# Arduino-Pro-Mini.net
KiCad netlist of a schematic drawn in EAGLE
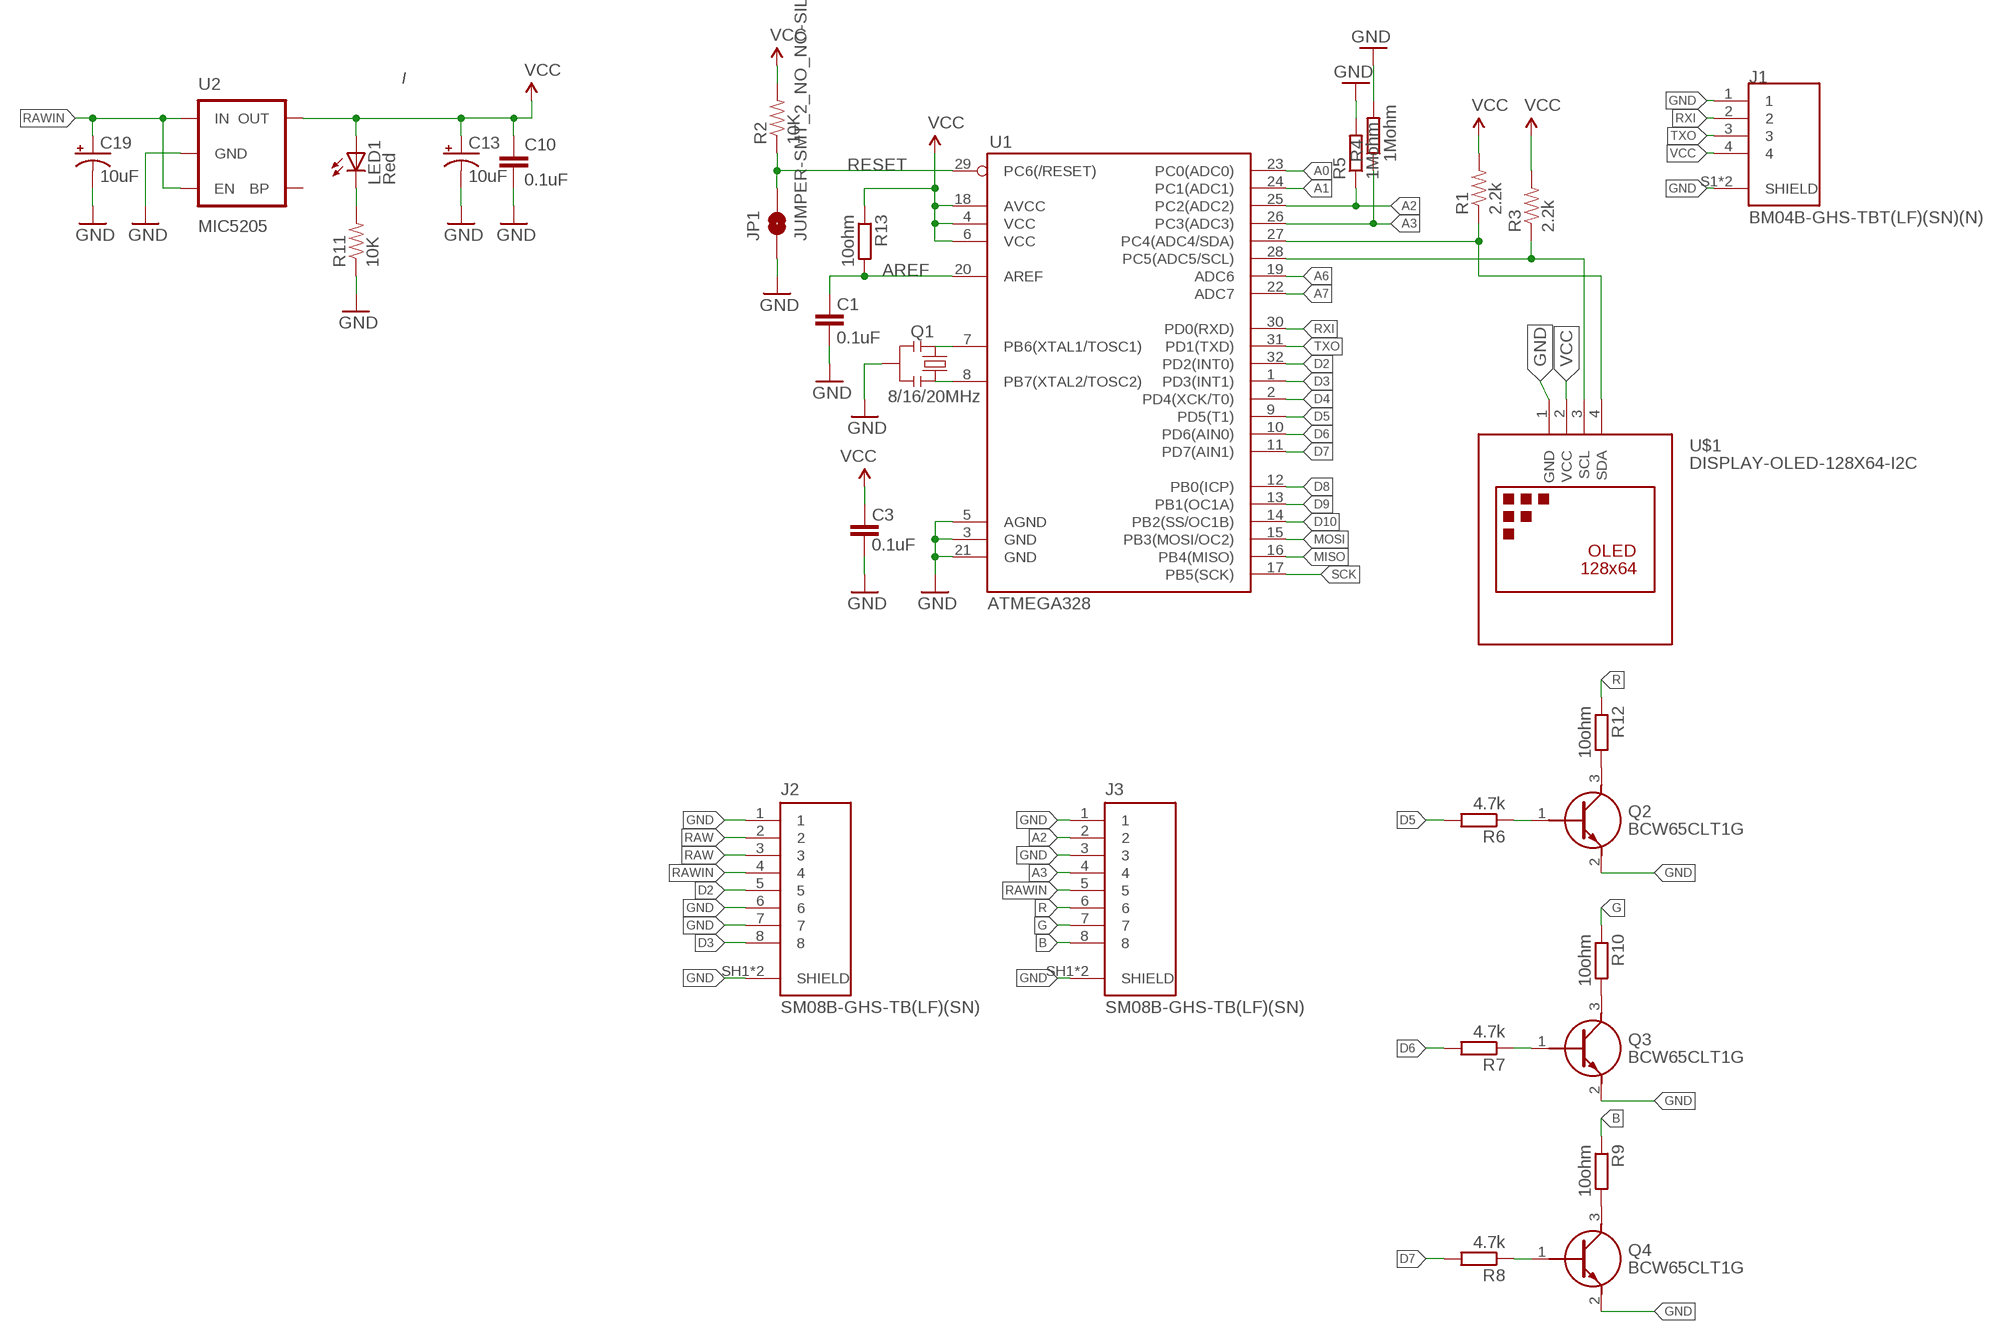
[diagram p0: schematic, sheet 1]

(export (version "E")
  (design (tool "Eeschema 10.0.6"))
  (components
    (comp (ref "C1")
      (value "0.1uF")
      (footprint "eagle-import:0603-CAP")
      (libsource (lib "eagle-import") (part "CAP0603-CAP"))
    )
    (comp (ref "C3")
      (value "0.1uF")
      (footprint "eagle-import:0603-CAP")
      (libsource (lib "eagle-import") (part "CAP0603-CAP"))
    )
    (comp (ref "C10")
      (value "0.1uF")
      (footprint "eagle-import:0603-CAP")
      (libsource (lib "eagle-import") (part "CAP0603-CAP"))
    )
    (comp (ref "C13")
      (value "10uF")
      (footprint "eagle-import:EIA3216")
      (libsource (lib "eagle-import") (part "CAP_POL1206"))
    )
    (comp (ref "C19")
      (value "10uF")
      (footprint "eagle-import:EIA3216")
      (libsource (lib "eagle-import") (part "CAP_POL1206"))
    )
    (comp (ref "J1")
      (value "BM04B-GHS-TBT(LF)(SN)(N)")
      (footprint "eagle-import:JST_BM04B-GHS-TBT(LF)(SN)(N)")
      (fields (field (name "MF") "JST Sales") (field (name "MP") "BM04B-GHS-TBT_LF__SN__N_"))
      (libsource (lib "eagle-import") (part "BM04B-GHS-TBT(LF)(SN)(N)"))
    )
    (comp (ref "J2")
      (value "SM08B-GHS-TB(LF)(SN)")
      (footprint "eagle-import:JST_SM08B-GHS-TB(LF)(SN)")
      (fields (field (name "MF") "JST Sales") (field (name "MP") "SM08B-GHS-TB_LF__SN_"))
      (libsource (lib "eagle-import") (part "SM08B-GHS-TB(LF)(SN)"))
    )
    (comp (ref "J3")
      (value "SM08B-GHS-TB(LF)(SN)")
      (footprint "eagle-import:JST_SM08B-GHS-TB(LF)(SN)")
      (fields (field (name "MF") "JST Sales") (field (name "MP") "SM08B-GHS-TB_LF__SN_"))
      (libsource (lib "eagle-import") (part "SM08B-GHS-TB(LF)(SN)"))
    )
    (comp (ref "JP1")
      (value "JUMPER-SMT_2_NO_NO-SILK")
      (footprint "eagle-import:SMT-JUMPER_2_NO_NO-SILK")
      (libsource (lib "eagle-import") (part "JUMPER-SMT_2_NO_NO-SILK"))
    )
    (comp (ref "LED1")
      (value "Red")
      (footprint "eagle-import:0603-LED-ALT1")
      (libsource (lib "eagle-import") (part "LED"))
    )
    (comp (ref "Q1")
      (value "8/16/20MHz")
      (footprint "eagle-import:RESONATOR-SMD-1_1")
      (libsource (lib "eagle-import") (part "RESONATOR1{colon}1"))
    )
    (comp (ref "Q2")
      (value "BCW65CLT1G")
      (footprint "eagle-import:SOT96P237X111-3N")
      (fields (field (name "MOUSER_PART_NUMBER") "863-BCW65CLT1G") (field (name "RS_PART_NUMBER") "8009686P"))
      (libsource (lib "eagle-import") (part "BCW65CLT1G"))
    )
    (comp (ref "Q3")
      (value "BCW65CLT1G")
      (footprint "eagle-import:SOT96P237X111-3N")
      (fields (field (name "MOUSER_PART_NUMBER") "863-BCW65CLT1G") (field (name "RS_PART_NUMBER") "8009686P"))
      (libsource (lib "eagle-import") (part "BCW65CLT1G"))
    )
    (comp (ref "Q4")
      (value "BCW65CLT1G")
      (footprint "eagle-import:SOT96P237X111-3N")
      (fields (field (name "MOUSER_PART_NUMBER") "863-BCW65CLT1G") (field (name "RS_PART_NUMBER") "8009686P"))
      (libsource (lib "eagle-import") (part "BCW65CLT1G"))
    )
    (comp (ref "R1")
      (value "2.2k")
      (footprint "eagle-import:0603-RES")
      (libsource (lib "eagle-import") (part "RESISTOR0603-RES"))
    )
    (comp (ref "R2")
      (value "10K")
      (footprint "eagle-import:0603-RES")
      (libsource (lib "eagle-import") (part "RESISTOR0603-RES"))
    )
    (comp (ref "R3")
      (value "2.2k")
      (footprint "eagle-import:0603-RES")
      (libsource (lib "eagle-import") (part "RESISTOR0603-RES"))
    )
    (comp (ref "R4")
      (value "1Mohm")
      (footprint "eagle-import:R0402")
      (libsource (lib "eagle-import") (part "RR0402"))
    )
    (comp (ref "R5")
      (value "1Mohm")
      (footprint "eagle-import:R0402")
      (libsource (lib "eagle-import") (part "RR0402"))
    )
    (comp (ref "R6")
      (value "4.7k")
      (footprint "eagle-import:R0402")
      (libsource (lib "eagle-import") (part "RR0402"))
    )
    (comp (ref "R7")
      (value "4.7k")
      (footprint "eagle-import:R0402")
      (libsource (lib "eagle-import") (part "RR0402"))
    )
    (comp (ref "R8")
      (value "4.7k")
      (footprint "eagle-import:R0402")
      (libsource (lib "eagle-import") (part "RR0402"))
    )
    (comp (ref "R9")
      (value "10ohm")
      (footprint "eagle-import:R0402")
      (libsource (lib "eagle-import") (part "RR0402"))
    )
    (comp (ref "R10")
      (value "10ohm")
      (footprint "eagle-import:R0402")
      (libsource (lib "eagle-import") (part "RR0402"))
    )
    (comp (ref "R11")
      (value "10K")
      (footprint "eagle-import:0603-RES")
      (libsource (lib "eagle-import") (part "RESISTOR0603-RES"))
    )
    (comp (ref "R12")
      (value "10ohm")
      (footprint "eagle-import:R0402")
      (libsource (lib "eagle-import") (part "RR0402"))
    )
    (comp (ref "R13")
      (value "10ohm")
      (footprint "eagle-import:R0402")
      (libsource (lib "eagle-import") (part "RR0402"))
    )
    (comp (ref "U$1")
      (value "DISPLAY-OLED-128X64-I2C")
      (footprint "eagle-import:DISPLAY-OLED-128X64-I2C")
      (libsource (lib "eagle-import") (part "DISPLAY-OLED-128X64-I2C"))
    )
    (comp (ref "U1")
      (value "ATMEGA328")
      (footprint "eagle-import:TQFP32-08")
      (libsource (lib "eagle-import") (part "ATMEGA168"))
    )
    (comp (ref "U2")
      (value "MIC5205")
      (footprint "eagle-import:SOT23-5")
      (libsource (lib "eagle-import") (part "V_REG_LDOSMD"))
    )
  )
  (nets
    (net (code "1") (name "/AREF") (class "Default")
      (node (ref "C1") (pin "2") (pinfunction "2_2") (pintype "passive"))
      (node (ref "R13") (pin "2") (pinfunction "2_2") (pintype "passive"))
      (node (ref "U1") (pin "20") (pinfunction "AREF_20") (pintype "bidirectional"))
    )
    (net (code "2") (name "/RESET") (class "Default")
      (node (ref "JP1") (pin "2") (pinfunction "2_2") (pintype "passive"))
      (node (ref "R2") (pin "1") (pinfunction "1_1") (pintype "passive"))
      (node (ref "U1") (pin "29") (pinfunction "PC6(/RESET)_29") (pintype "bidirectional"))
    )
    (net (code "3") (name "A0") (class "Default")
      (node (ref "U1") (pin "23") (pinfunction "PC0(ADC0)_23") (pintype "bidirectional"))
    )
    (net (code "4") (name "A1") (class "Default")
      (node (ref "U1") (pin "24") (pinfunction "PC1(ADC1)_24") (pintype "bidirectional"))
    )
    (net (code "5") (name "A2") (class "Default")
      (node (ref "J3") (pin "2") (pinfunction "2_2") (pintype "passive"))
      (node (ref "R5") (pin "1") (pinfunction "1_1") (pintype "passive"))
      (node (ref "U1") (pin "25") (pinfunction "PC2(ADC2)_25") (pintype "bidirectional"))
    )
    (net (code "6") (name "A3") (class "Default")
      (node (ref "J3") (pin "4") (pinfunction "4_4") (pintype "passive"))
      (node (ref "R4") (pin "1") (pinfunction "1_1") (pintype "passive"))
      (node (ref "U1") (pin "26") (pinfunction "PC3(ADC3)_26") (pintype "bidirectional"))
    )
    (net (code "7") (name "A6") (class "Default")
      (node (ref "U1") (pin "19") (pinfunction "ADC6_19") (pintype "bidirectional"))
    )
    (net (code "8") (name "A7") (class "Default")
      (node (ref "U1") (pin "22") (pinfunction "ADC7_22") (pintype "bidirectional"))
    )
    (net (code "9") (name "B") (class "Default")
      (node (ref "J3") (pin "8") (pinfunction "8_8") (pintype "passive"))
      (node (ref "R9") (pin "1") (pinfunction "1_1") (pintype "passive"))
    )
    (net (code "10") (name "D2") (class "Default")
      (node (ref "J2") (pin "5") (pinfunction "5_5") (pintype "passive"))
      (node (ref "U1") (pin "32") (pinfunction "PD2(INT0)_32") (pintype "bidirectional"))
    )
    (net (code "11") (name "D3") (class "Default")
      (node (ref "J2") (pin "8") (pinfunction "8_8") (pintype "passive"))
      (node (ref "U1") (pin "1") (pinfunction "PD3(INT1)_1") (pintype "bidirectional"))
    )
    (net (code "12") (name "D4") (class "Default")
      (node (ref "U1") (pin "2") (pinfunction "PD4(XCK/T0)_2") (pintype "bidirectional"))
    )
    (net (code "13") (name "D5") (class "Default")
      (node (ref "R6") (pin "2") (pinfunction "2_2") (pintype "passive"))
      (node (ref "U1") (pin "9") (pinfunction "PD5(T1)_9") (pintype "bidirectional"))
    )
    (net (code "14") (name "D6") (class "Default")
      (node (ref "R7") (pin "2") (pinfunction "2_2") (pintype "passive"))
      (node (ref "U1") (pin "10") (pinfunction "PD6(AIN0)_10") (pintype "bidirectional"))
    )
    (net (code "15") (name "D7") (class "Default")
      (node (ref "R8") (pin "2") (pinfunction "2_2") (pintype "passive"))
      (node (ref "U1") (pin "11") (pinfunction "PD7(AIN1)_11") (pintype "bidirectional"))
    )
    (net (code "16") (name "D8") (class "Default")
      (node (ref "U1") (pin "12") (pinfunction "PB0(ICP)_12") (pintype "bidirectional"))
    )
    (net (code "17") (name "D9") (class "Default")
      (node (ref "U1") (pin "13") (pinfunction "PB1(OC1A)_13") (pintype "bidirectional"))
    )
    (net (code "18") (name "D10") (class "Default")
      (node (ref "U1") (pin "14") (pinfunction "PB2(SS/OC1B)_14") (pintype "bidirectional"))
    )
    (net (code "19") (name "G") (class "Default")
      (node (ref "J3") (pin "7") (pinfunction "7_7") (pintype "passive"))
      (node (ref "R10") (pin "1") (pinfunction "1_1") (pintype "passive"))
    )
    (net (code "20") (name "GND") (class "Default")
      (node (ref "C1") (pin "1") (pinfunction "1_1") (pintype "passive"))
      (node (ref "C10") (pin "2") (pinfunction "2_2") (pintype "passive"))
      (node (ref "C13") (pin "C") (pinfunction "-_C") (pintype "passive"))
      (node (ref "C19") (pin "C") (pinfunction "-_C") (pintype "passive"))
      (node (ref "C3") (pin "1") (pinfunction "1_1") (pintype "passive"))
      (node (ref "J1") (pin "1") (pinfunction "1_1") (pintype "passive"))
      (node (ref "J1") (pin "S1") (pinfunction "SHIELD_S1") (pintype "passive"))
      (node (ref "J1") (pin "S2") (pinfunction "SHIELD_S2") (pintype "passive"))
      (node (ref "J2") (pin "1") (pinfunction "1_1") (pintype "passive"))
      (node (ref "J2") (pin "6") (pinfunction "6_6") (pintype "passive"))
      (node (ref "J2") (pin "7") (pinfunction "7_7") (pintype "passive"))
      (node (ref "J2") (pin "SH1") (pinfunction "SHIELD_SH1") (pintype "passive"))
      (node (ref "J2") (pin "SH2") (pinfunction "SHIELD_SH2") (pintype "passive"))
      (node (ref "J3") (pin "1") (pinfunction "1_1") (pintype "passive"))
      (node (ref "J3") (pin "3") (pinfunction "3_3") (pintype "passive"))
      (node (ref "J3") (pin "SH1") (pinfunction "SHIELD_SH1") (pintype "passive"))
      (node (ref "J3") (pin "SH2") (pinfunction "SHIELD_SH2") (pintype "passive"))
      (node (ref "JP1") (pin "1") (pinfunction "1_1") (pintype "passive"))
      (node (ref "Q1") (pin "2") (pinfunction "2_2") (pintype "passive"))
      (node (ref "Q2") (pin "2") (pinfunction "E_2") (pintype "bidirectional"))
      (node (ref "Q3") (pin "2") (pinfunction "E_2") (pintype "bidirectional"))
      (node (ref "Q4") (pin "2") (pinfunction "E_2") (pintype "bidirectional"))
      (node (ref "R11") (pin "1") (pinfunction "1_1") (pintype "passive"))
      (node (ref "R4") (pin "2") (pinfunction "2_2") (pintype "passive"))
      (node (ref "R5") (pin "2") (pinfunction "2_2") (pintype "passive"))
      (node (ref "U$1") (pin "1") (pinfunction "GND_1") (pintype "power_in"))
      (node (ref "U1") (pin "21") (pinfunction "GND_21") (pintype "bidirectional"))
      (node (ref "U1") (pin "3") (pinfunction "GND_3") (pintype "bidirectional"))
      (node (ref "U1") (pin "5") (pinfunction "AGND_5") (pintype "bidirectional"))
      (node (ref "U2") (pin "2") (pinfunction "GND_2") (pintype "input"))
    )
    (net (code "21") (name "MISO") (class "Default")
      (node (ref "U1") (pin "16") (pinfunction "PB4(MISO)_16") (pintype "bidirectional"))
    )
    (net (code "22") (name "MOSI") (class "Default")
      (node (ref "U1") (pin "15") (pinfunction "PB3(MOSI/OC2)_15") (pintype "bidirectional"))
    )
    (net (code "23") (name "Net-(LED1-PadC)") (class "Default")
      (node (ref "LED1") (pin "C") (pinfunction "C_C") (pintype "passive"))
      (node (ref "R11") (pin "2") (pinfunction "2_2") (pintype "passive"))
    )
    (net (code "24") (name "Net-(Q2-B)") (class "Default")
      (node (ref "Q2") (pin "1") (pinfunction "B_1") (pintype "bidirectional"))
      (node (ref "R6") (pin "1") (pinfunction "1_1") (pintype "passive"))
    )
    (net (code "25") (name "Net-(Q2-C)") (class "Default")
      (node (ref "Q2") (pin "3") (pinfunction "C_3") (pintype "bidirectional"))
      (node (ref "R12") (pin "2") (pinfunction "2_2") (pintype "passive"))
    )
    (net (code "26") (name "Net-(Q3-B)") (class "Default")
      (node (ref "Q3") (pin "1") (pinfunction "B_1") (pintype "bidirectional"))
      (node (ref "R7") (pin "1") (pinfunction "1_1") (pintype "passive"))
    )
    (net (code "27") (name "Net-(Q3-C)") (class "Default")
      (node (ref "Q3") (pin "3") (pinfunction "C_3") (pintype "bidirectional"))
      (node (ref "R10") (pin "2") (pinfunction "2_2") (pintype "passive"))
    )
    (net (code "28") (name "Net-(Q4-B)") (class "Default")
      (node (ref "Q4") (pin "1") (pinfunction "B_1") (pintype "bidirectional"))
      (node (ref "R8") (pin "1") (pinfunction "1_1") (pintype "passive"))
    )
    (net (code "29") (name "Net-(Q4-C)") (class "Default")
      (node (ref "Q4") (pin "3") (pinfunction "C_3") (pintype "bidirectional"))
      (node (ref "R9") (pin "2") (pinfunction "2_2") (pintype "passive"))
    )
    (net (code "30") (name "Net-(U$1-SCL)") (class "Default")
      (node (ref "R3") (pin "1") (pinfunction "1_1") (pintype "passive"))
      (node (ref "U$1") (pin "3") (pinfunction "SCL_3") (pintype "bidirectional"))
      (node (ref "U1") (pin "28") (pinfunction "PC5(ADC5/SCL)_28") (pintype "bidirectional"))
    )
    (net (code "31") (name "Net-(U$1-SDA)") (class "Default")
      (node (ref "R1") (pin "1") (pinfunction "1_1") (pintype "passive"))
      (node (ref "U$1") (pin "4") (pinfunction "SDA_4") (pintype "bidirectional"))
      (node (ref "U1") (pin "27") (pinfunction "PC4(ADC4/SDA)_27") (pintype "bidirectional"))
    )
    (net (code "32") (name "Net-(U1-PB6(XTAL1{slash}TOSC1))") (class "Default")
      (node (ref "Q1") (pin "1") (pinfunction "1_1") (pintype "passive"))
      (node (ref "U1") (pin "7") (pinfunction "PB6(XTAL1/TOSC1)_7") (pintype "bidirectional"))
    )
    (net (code "33") (name "Net-(U1-PB7(XTAL2{slash}TOSC2))") (class "Default")
      (node (ref "Q1") (pin "3") (pinfunction "3_3") (pintype "passive"))
      (node (ref "U1") (pin "8") (pinfunction "PB7(XTAL2/TOSC2)_8") (pintype "bidirectional"))
    )
    (net (code "34") (name "R") (class "Default")
      (node (ref "J3") (pin "6") (pinfunction "6_6") (pintype "passive"))
      (node (ref "R12") (pin "1") (pinfunction "1_1") (pintype "passive"))
    )
    (net (code "35") (name "RAW") (class "Default")
      (node (ref "J2") (pin "2") (pinfunction "2_2") (pintype "passive"))
      (node (ref "J2") (pin "3") (pinfunction "3_3") (pintype "passive"))
    )
    (net (code "36") (name "RAWIN") (class "Default")
      (node (ref "C19") (pin "A") (pinfunction "+_A") (pintype "passive"))
      (node (ref "J2") (pin "4") (pinfunction "4_4") (pintype "passive"))
      (node (ref "J3") (pin "5") (pinfunction "5_5") (pintype "passive"))
      (node (ref "U2") (pin "1") (pinfunction "IN_1") (pintype "input"))
      (node (ref "U2") (pin "3") (pinfunction "EN_3") (pintype "input"))
    )
    (net (code "37") (name "RXI") (class "Default")
      (node (ref "J1") (pin "2") (pinfunction "2_2") (pintype "passive"))
      (node (ref "U1") (pin "30") (pinfunction "PD0(RXD)_30") (pintype "bidirectional"))
    )
    (net (code "38") (name "SCK") (class "Default")
      (node (ref "U1") (pin "17") (pinfunction "PB5(SCK)_17") (pintype "bidirectional"))
    )
    (net (code "39") (name "TXO") (class "Default")
      (node (ref "J1") (pin "3") (pinfunction "3_3") (pintype "passive"))
      (node (ref "U1") (pin "31") (pinfunction "PD1(TXD)_31") (pintype "bidirectional"))
    )
    (net (code "40") (name "VCC") (class "Default")
      (node (ref "C10") (pin "1") (pinfunction "1_1") (pintype "passive"))
      (node (ref "C13") (pin "A") (pinfunction "+_A") (pintype "passive"))
      (node (ref "C3") (pin "2") (pinfunction "2_2") (pintype "passive"))
      (node (ref "J1") (pin "4") (pinfunction "4_4") (pintype "passive"))
      (node (ref "LED1") (pin "A") (pinfunction "A_A") (pintype "passive"))
      (node (ref "R1") (pin "2") (pinfunction "2_2") (pintype "passive"))
      (node (ref "R13") (pin "1") (pinfunction "1_1") (pintype "passive"))
      (node (ref "R2") (pin "2") (pinfunction "2_2") (pintype "passive"))
      (node (ref "R3") (pin "2") (pinfunction "2_2") (pintype "passive"))
      (node (ref "U$1") (pin "2") (pinfunction "VCC_2") (pintype "power_in"))
      (node (ref "U1") (pin "18") (pinfunction "AVCC_18") (pintype "bidirectional"))
      (node (ref "U1") (pin "4") (pinfunction "VCC_4") (pintype "bidirectional"))
      (node (ref "U1") (pin "6") (pinfunction "VCC_6") (pintype "bidirectional"))
      (node (ref "U2") (pin "5") (pinfunction "OUT_5") (pintype "passive"))
    )
    (net (code "41") (name "unconnected-(U2-BP-Pad4)") (class "Default")
      (node (ref "U2") (pin "4") (pinfunction "BP_4") (pintype "input"))
    )
  )
)
